# preamp.net
KiCad netlist of a schematic drawn in EAGLE
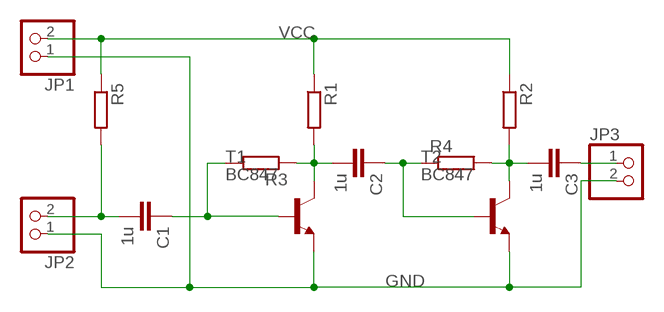
[diagram p0: schematic, sheet 1]

(export (version "E")
  (design (tool "Eeschema 10.0.6"))
  (components
    (comp (ref "C1")
      (value "1u")
      (footprint "eagle-import:C0805")
      (libsource (lib "eagle-import") (part "C-EUC0805"))
    )
    (comp (ref "C2")
      (value "1u")
      (footprint "eagle-import:C0805")
      (libsource (lib "eagle-import") (part "C-EUC0805"))
    )
    (comp (ref "C3")
      (value "1u")
      (footprint "eagle-import:C0805")
      (libsource (lib "eagle-import") (part "C-EUC0805"))
    )
    (comp (ref "JP1")
      (value "PINHD-1X2")
      (footprint "eagle-import:1X02")
      (libsource (lib "eagle-import") (part "PINHD-1X2"))
    )
    (comp (ref "JP2")
      (value "PINHD-1X2")
      (footprint "eagle-import:1X02")
      (libsource (lib "eagle-import") (part "PINHD-1X2"))
    )
    (comp (ref "JP3")
      (value "PINHD-1X2")
      (footprint "eagle-import:1X02")
      (libsource (lib "eagle-import") (part "PINHD-1X2"))
    )
    (comp (ref "R1")
      (value "R-EU_R0805")
      (footprint "eagle-import:R0805")
      (libsource (lib "eagle-import") (part "R-EU_R0805"))
    )
    (comp (ref "R2")
      (value "R-EU_R0805")
      (footprint "eagle-import:R0805")
      (libsource (lib "eagle-import") (part "R-EU_R0805"))
    )
    (comp (ref "R3")
      (value "R-EU_R0805")
      (footprint "eagle-import:R0805")
      (libsource (lib "eagle-import") (part "R-EU_R0805"))
    )
    (comp (ref "R4")
      (value "R-EU_R0805")
      (footprint "eagle-import:R0805")
      (libsource (lib "eagle-import") (part "R-EU_R0805"))
    )
    (comp (ref "R5")
      (value "R-EU_R0805")
      (footprint "eagle-import:R0805")
      (libsource (lib "eagle-import") (part "R-EU_R0805"))
    )
    (comp (ref "T1")
      (value "BC847")
      (footprint "eagle-import:SOT23")
      (libsource (lib "eagle-import") (part "BC847"))
    )
    (comp (ref "T2")
      (value "BC847")
      (footprint "eagle-import:SOT23")
      (libsource (lib "eagle-import") (part "BC847"))
    )
  )
  (nets
    (net (code "1") (name "/GND") (class "Default")
      (node (ref "JP1") (pin "1") (pinfunction "1_1") (pintype "passive"))
      (node (ref "JP2") (pin "1") (pinfunction "1_1") (pintype "passive"))
      (node (ref "JP3") (pin "2") (pinfunction "2_2") (pintype "passive"))
      (node (ref "T1") (pin "2") (pinfunction "E_2") (pintype "passive"))
      (node (ref "T2") (pin "2") (pinfunction "E_2") (pintype "passive"))
    )
    (net (code "2") (name "/VCC") (class "Default")
      (node (ref "JP1") (pin "2") (pinfunction "2_2") (pintype "passive"))
      (node (ref "R1") (pin "1") (pinfunction "1_1") (pintype "passive"))
      (node (ref "R2") (pin "1") (pinfunction "1_1") (pintype "passive"))
      (node (ref "R5") (pin "1") (pinfunction "1_1") (pintype "passive"))
    )
    (net (code "3") (name "Net-(C1-Pad2)") (class "Default")
      (node (ref "C1") (pin "2") (pinfunction "2_2") (pintype "passive"))
      (node (ref "JP2") (pin "2") (pinfunction "2_2") (pintype "passive"))
      (node (ref "R5") (pin "2") (pinfunction "2_2") (pintype "passive"))
    )
    (net (code "4") (name "Net-(C3-Pad1)") (class "Default")
      (node (ref "C3") (pin "1") (pinfunction "1_1") (pintype "passive"))
      (node (ref "JP3") (pin "1") (pinfunction "1_1") (pintype "passive"))
    )
    (net (code "5") (name "Net-(T1-B)") (class "Default")
      (node (ref "C1") (pin "1") (pinfunction "1_1") (pintype "passive"))
      (node (ref "R3") (pin "2") (pinfunction "2_2") (pintype "passive"))
      (node (ref "T1") (pin "1") (pinfunction "B_1") (pintype "passive"))
    )
    (net (code "6") (name "Net-(T1-C)") (class "Default")
      (node (ref "C2") (pin "2") (pinfunction "2_2") (pintype "passive"))
      (node (ref "R1") (pin "2") (pinfunction "2_2") (pintype "passive"))
      (node (ref "R3") (pin "1") (pinfunction "1_1") (pintype "passive"))
      (node (ref "T1") (pin "3") (pinfunction "C_3") (pintype "passive"))
    )
    (net (code "7") (name "Net-(T2-B)") (class "Default")
      (node (ref "C2") (pin "1") (pinfunction "1_1") (pintype "passive"))
      (node (ref "R4") (pin "1") (pinfunction "1_1") (pintype "passive"))
      (node (ref "T2") (pin "1") (pinfunction "B_1") (pintype "passive"))
    )
    (net (code "8") (name "Net-(T2-C)") (class "Default")
      (node (ref "C3") (pin "2") (pinfunction "2_2") (pintype "passive"))
      (node (ref "R2") (pin "2") (pinfunction "2_2") (pintype "passive"))
      (node (ref "R4") (pin "2") (pinfunction "2_2") (pintype "passive"))
      (node (ref "T2") (pin "3") (pinfunction "C_3") (pintype "passive"))
    )
  )
)
